# EOPTO01.net
KiCad netlist of a schematic drawn in EAGLE
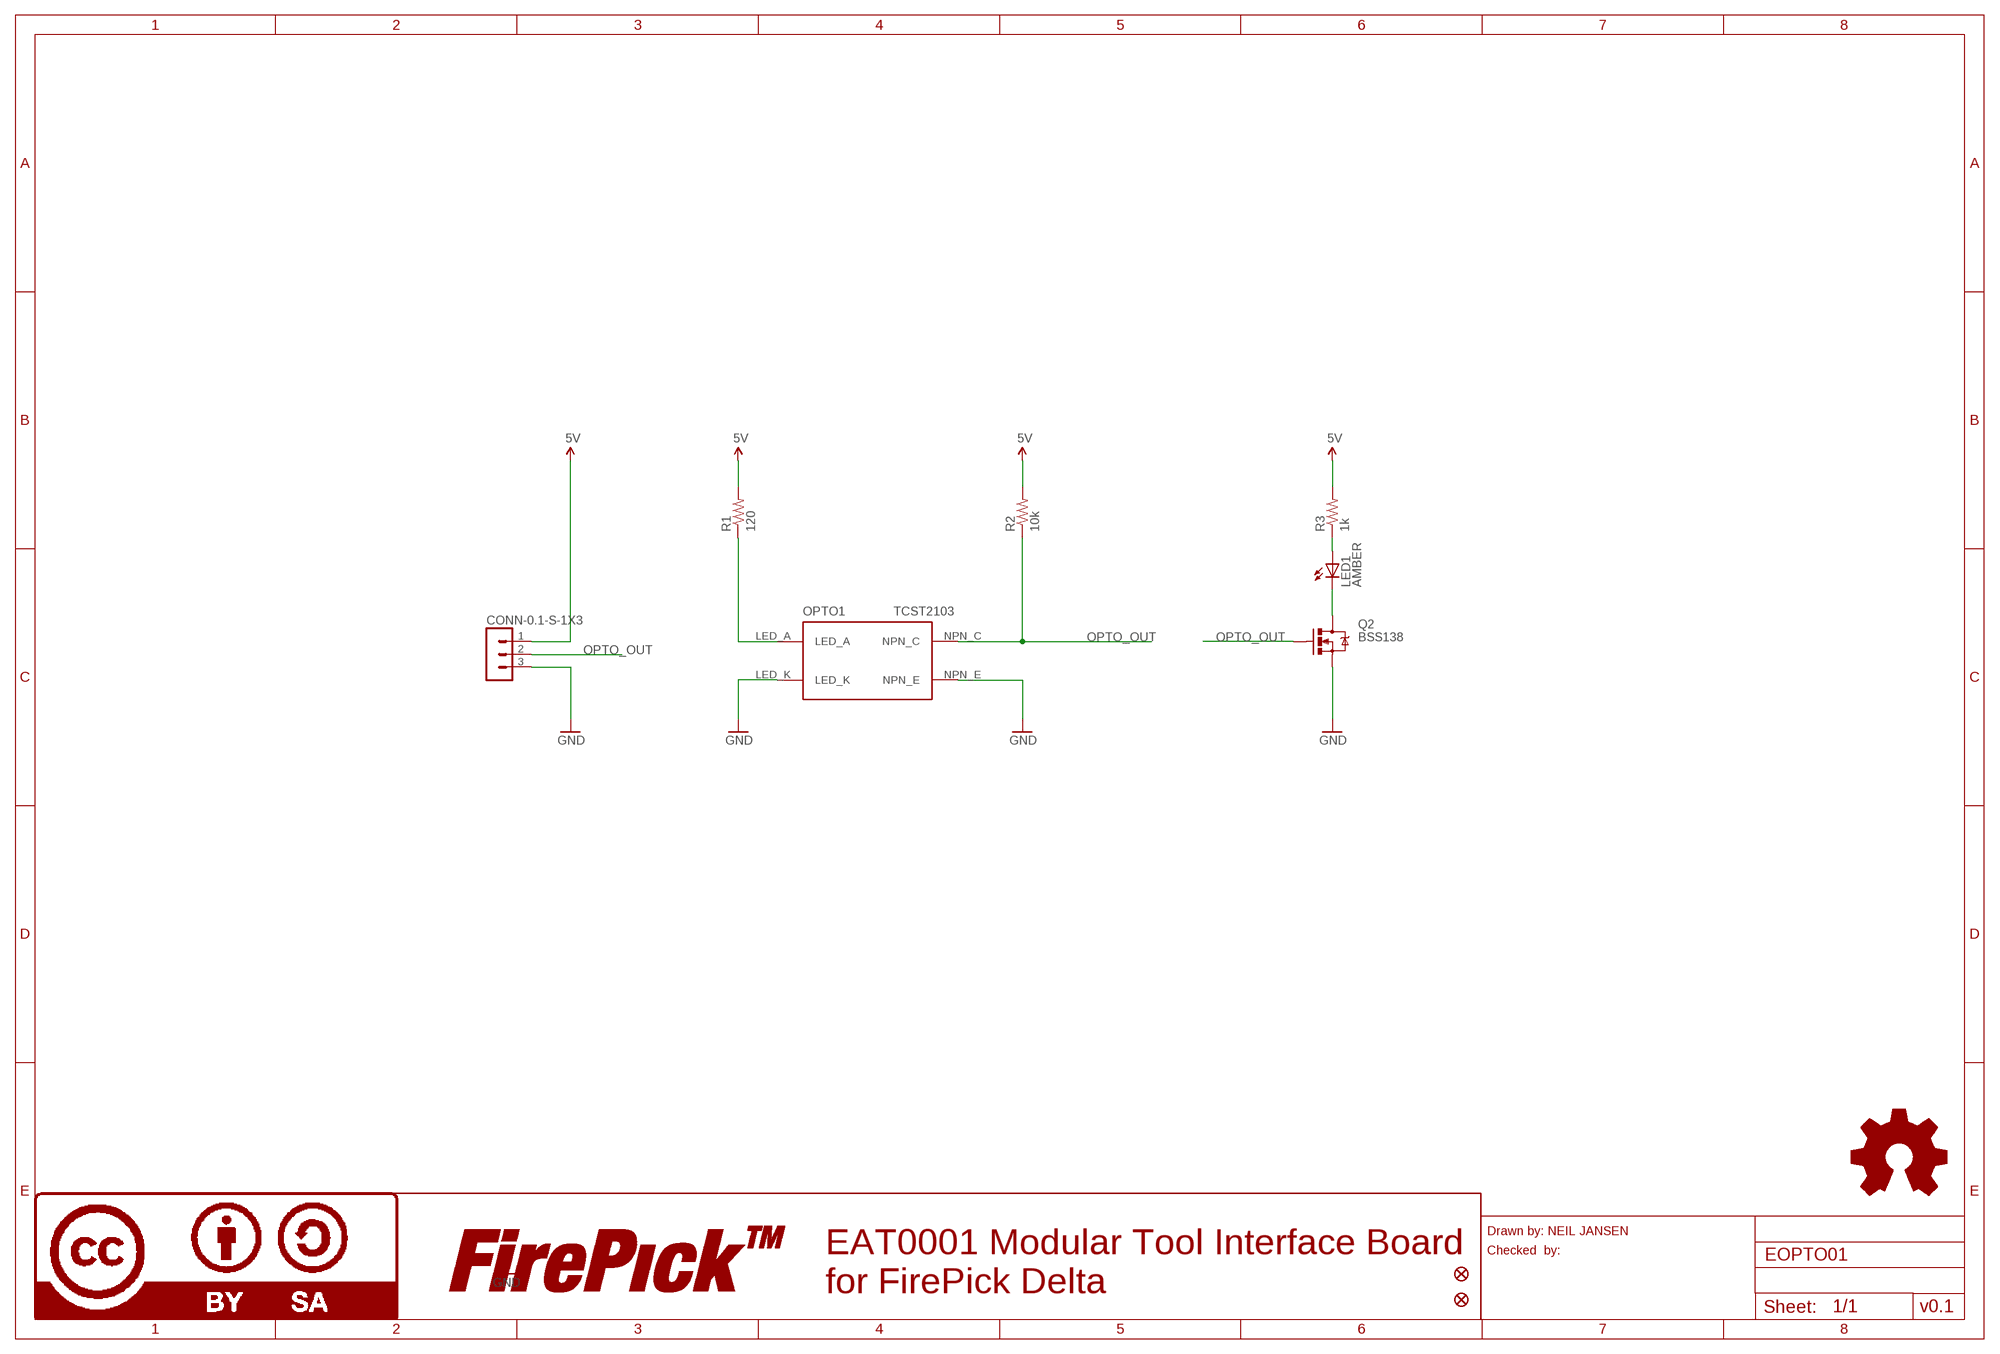
[diagram p0: schematic, sheet 1]

(export (version "E")
  (design (tool "Eeschema 10.0.6"))
  (components
    (comp (ref "FID3")
      (value "FIDUCIAL1X2")
      (footprint "eagle-import:FIDUCIAL-1X2")
      (libsource (lib "eagle-import") (part "FIDUCIAL1X2"))
    )
    (comp (ref "FID4")
      (value "FIDUCIAL1X2")
      (footprint "eagle-import:FIDUCIAL-1X2")
      (libsource (lib "eagle-import") (part "FIDUCIAL1X2"))
    )
    (comp (ref "J1")
      (value "CONN-0.1-S-1X3")
      (footprint "eagle-import:MA03-1")
      (fields (field (name "PARTNO") "CONN-0.1-RA-1X3"))
      (libsource (lib "eagle-import") (part "MA03-1"))
    )
    (comp (ref "LED1")
      (value "AMBER")
      (footprint "eagle-import:LED-1206")
      (fields (field (name "PARTNO") "LTST-C150AKT"))
      (libsource (lib "eagle-import") (part "LED1206"))
    )
    (comp (ref "LOGO4")
      (value "LOGO-FIREPICKMEDIUM")
      (footprint "eagle-import:LOGO-FIREPICK-MEDIUM")
      (libsource (lib "eagle-import") (part "LOGO-FIREPICKMEDIUM"))
    )
    (comp (ref "LOGO5")
      (value "LOGO-OSHWSMALL")
      (footprint "eagle-import:LOGO-OSHW-SMALL")
      (libsource (lib "eagle-import") (part "LOGO-OSHWSMALL"))
    )
    (comp (ref "LOGO6")
      (value "LOGO-CC-BY-SAMEDIUM")
      (footprint "eagle-import:LOGO-CC-BY-SA-MEDIUM")
      (libsource (lib "eagle-import") (part "LOGO-CC-BY-SAMEDIUM"))
    )
    (comp (ref "OPTO1")
      (value "TCST2103")
      (footprint "eagle-import:TCST2013")
      (libsource (lib "eagle-import") (part "TCST2103"))
    )
    (comp (ref "Q2")
      (value "BSS138")
      (footprint "eagle-import:SOT23")
      (libsource (lib "eagle-import") (part "MOSFET-NCHANNELBSS138"))
    )
    (comp (ref "R1")
      (value "120")
      (footprint "eagle-import:0805")
      (fields (field (name "PARTNO") "RC0805FR-07120RL"))
      (libsource (lib "eagle-import") (part "RESISTOR0805-RES"))
    )
    (comp (ref "R2")
      (value "10k")
      (footprint "eagle-import:0805")
      (fields (field (name "PARTNO") "RC0805FR-0710KL"))
      (libsource (lib "eagle-import") (part "RESISTOR0805-RES"))
    )
    (comp (ref "R3")
      (value "1k")
      (footprint "eagle-import:0805")
      (fields (field (name "PARTNO") "RC0805FR-071KL"))
      (libsource (lib "eagle-import") (part "RESISTOR0805-RES"))
    )
  )
  (nets
    (net (code "1") (name "/OPTO_OUT") (class "Default")
      (node (ref "J1") (pin "2") (pinfunction "2_2") (pintype "passive"))
      (node (ref "OPTO1") (pin "NPN_C") (pinfunction "NPN_C_NPN_C") (pintype "bidirectional"))
      (node (ref "Q2") (pin "1") (pinfunction "G_1") (pintype "passive"))
      (node (ref "R2") (pin "1") (pinfunction "1_1") (pintype "passive"))
    )
    (net (code "2") (name "5V") (class "Default")
      (node (ref "J1") (pin "1") (pinfunction "1_1") (pintype "passive"))
      (node (ref "R1") (pin "2") (pinfunction "2_2") (pintype "passive"))
      (node (ref "R2") (pin "2") (pinfunction "2_2") (pintype "passive"))
      (node (ref "R3") (pin "2") (pinfunction "2_2") (pintype "passive"))
    )
    (net (code "3") (name "GND") (class "Default")
      (node (ref "J1") (pin "3") (pinfunction "3_3") (pintype "passive"))
      (node (ref "OPTO1") (pin "LED_K") (pinfunction "LED_K_LED_K") (pintype "bidirectional"))
      (node (ref "OPTO1") (pin "NPN_E") (pinfunction "NPN_E_NPN_E") (pintype "bidirectional"))
      (node (ref "Q2") (pin "2") (pinfunction "S_2") (pintype "passive"))
    )
    (net (code "4") (name "Net-(LED1-PadA)") (class "Default")
      (node (ref "LED1") (pin "A") (pinfunction "A_A") (pintype "passive"))
      (node (ref "R3") (pin "1") (pinfunction "1_1") (pintype "passive"))
    )
    (net (code "5") (name "Net-(OPTO1-PadLED_A)") (class "Default")
      (node (ref "OPTO1") (pin "LED_A") (pinfunction "LED_A_LED_A") (pintype "bidirectional"))
      (node (ref "R1") (pin "1") (pinfunction "1_1") (pintype "passive"))
    )
    (net (code "6") (name "Net-(Q2-D)") (class "Default")
      (node (ref "LED1") (pin "C") (pinfunction "C_C") (pintype "passive"))
      (node (ref "Q2") (pin "3") (pinfunction "D_3") (pintype "passive"))
    )
  )
)
